# BusConOld.net
KiCad netlist of a schematic drawn in EAGLE
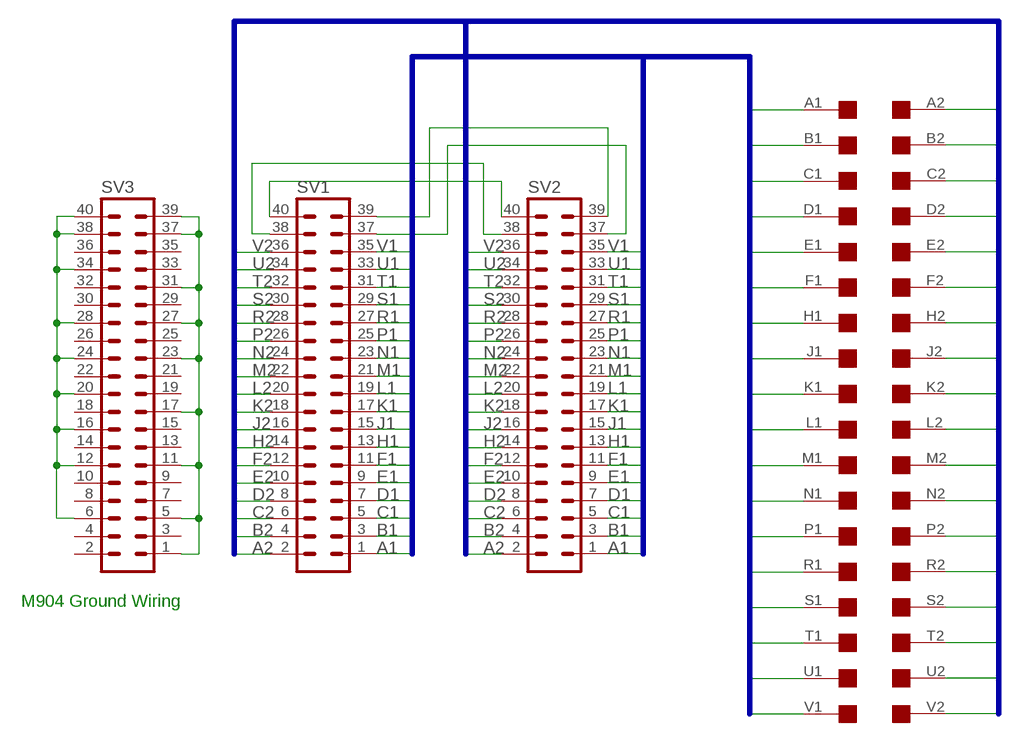
[diagram p0: schematic, sheet 1]

(export (version "E")
  (design (tool "Eeschema 10.0.6"))
  (components
    (comp (ref "SV1")
      (value "MA20-2W")
      (footprint "eagle-import:MA20-2W")
      (libsource (lib "eagle-import") (part "MA20-2W"))
    )
    (comp (ref "SV2")
      (value "MA20-2W")
      (footprint "eagle-import:MA20-2W")
      (libsource (lib "eagle-import") (part "MA20-2W"))
    )
    (comp (ref "SV3")
      (value "MA20-2W")
      (footprint "eagle-import:MA20-2W")
      (libsource (lib "eagle-import") (part "MA20-2W"))
    )
    (comp (ref "U$1")
      (value "DEC-FLIPCHIP")
      (footprint "eagle-import:DEC-FLIPCHIP")
      (libsource (lib "eagle-import") (part "DEC-FLIPCHIP"))
    )
  )
  (nets
    (net (code "1") (name "/A1") (class "Default")
      (node (ref "SV1") (pin "1") (pinfunction "1_1") (pintype "passive"))
      (node (ref "SV2") (pin "1") (pinfunction "1_1") (pintype "passive"))
      (node (ref "U$1") (pin "A1") (pinfunction "A1_A1") (pintype "passive"))
    )
    (net (code "2") (name "/A2") (class "Default")
      (node (ref "SV1") (pin "2") (pinfunction "2_2") (pintype "passive"))
      (node (ref "SV2") (pin "2") (pinfunction "2_2") (pintype "passive"))
      (node (ref "U$1") (pin "A2") (pinfunction "A2_A2") (pintype "passive"))
    )
    (net (code "3") (name "/B1") (class "Default")
      (node (ref "SV1") (pin "3") (pinfunction "3_3") (pintype "passive"))
      (node (ref "SV2") (pin "3") (pinfunction "3_3") (pintype "passive"))
      (node (ref "U$1") (pin "B1") (pinfunction "B1_B1") (pintype "passive"))
    )
    (net (code "4") (name "/B2") (class "Default")
      (node (ref "SV1") (pin "4") (pinfunction "4_4") (pintype "passive"))
      (node (ref "SV2") (pin "4") (pinfunction "4_4") (pintype "passive"))
      (node (ref "U$1") (pin "B2") (pinfunction "B2_B2") (pintype "passive"))
    )
    (net (code "5") (name "/C1") (class "Default")
      (node (ref "SV1") (pin "5") (pinfunction "5_5") (pintype "passive"))
      (node (ref "SV2") (pin "5") (pinfunction "5_5") (pintype "passive"))
      (node (ref "U$1") (pin "C1") (pinfunction "C1_C1") (pintype "passive"))
    )
    (net (code "6") (name "/C2") (class "Default")
      (node (ref "SV1") (pin "6") (pinfunction "6_6") (pintype "passive"))
      (node (ref "SV2") (pin "6") (pinfunction "6_6") (pintype "passive"))
      (node (ref "U$1") (pin "C2") (pinfunction "C2_C2") (pintype "passive"))
    )
    (net (code "7") (name "/D1") (class "Default")
      (node (ref "SV1") (pin "7") (pinfunction "7_7") (pintype "passive"))
      (node (ref "SV2") (pin "7") (pinfunction "7_7") (pintype "passive"))
      (node (ref "U$1") (pin "D1") (pinfunction "D1_D1") (pintype "passive"))
    )
    (net (code "8") (name "/D2") (class "Default")
      (node (ref "SV1") (pin "8") (pinfunction "8_8") (pintype "passive"))
      (node (ref "SV2") (pin "8") (pinfunction "8_8") (pintype "passive"))
      (node (ref "U$1") (pin "D2") (pinfunction "D2_D2") (pintype "passive"))
    )
    (net (code "9") (name "/E1") (class "Default")
      (node (ref "SV1") (pin "9") (pinfunction "9_9") (pintype "passive"))
      (node (ref "SV2") (pin "9") (pinfunction "9_9") (pintype "passive"))
      (node (ref "U$1") (pin "E1") (pinfunction "E1_E1") (pintype "passive"))
    )
    (net (code "10") (name "/E2") (class "Default")
      (node (ref "SV1") (pin "10") (pinfunction "10_10") (pintype "passive"))
      (node (ref "SV2") (pin "10") (pinfunction "10_10") (pintype "passive"))
      (node (ref "U$1") (pin "E2") (pinfunction "E2_E2") (pintype "passive"))
    )
    (net (code "11") (name "/F1") (class "Default")
      (node (ref "SV1") (pin "11") (pinfunction "11_11") (pintype "passive"))
      (node (ref "SV2") (pin "11") (pinfunction "11_11") (pintype "passive"))
      (node (ref "U$1") (pin "F1") (pinfunction "F1_F1") (pintype "passive"))
    )
    (net (code "12") (name "/F2") (class "Default")
      (node (ref "SV1") (pin "12") (pinfunction "12_12") (pintype "passive"))
      (node (ref "SV2") (pin "12") (pinfunction "12_12") (pintype "passive"))
      (node (ref "U$1") (pin "F2") (pinfunction "F2_F2") (pintype "passive"))
    )
    (net (code "13") (name "/H1") (class "Default")
      (node (ref "SV1") (pin "13") (pinfunction "13_13") (pintype "passive"))
      (node (ref "SV2") (pin "13") (pinfunction "13_13") (pintype "passive"))
      (node (ref "U$1") (pin "H1") (pinfunction "H1_H1") (pintype "passive"))
    )
    (net (code "14") (name "/H2") (class "Default")
      (node (ref "SV1") (pin "14") (pinfunction "14_14") (pintype "passive"))
      (node (ref "SV2") (pin "14") (pinfunction "14_14") (pintype "passive"))
      (node (ref "U$1") (pin "H2") (pinfunction "H2_H2") (pintype "passive"))
    )
    (net (code "15") (name "/J1") (class "Default")
      (node (ref "SV1") (pin "15") (pinfunction "15_15") (pintype "passive"))
      (node (ref "SV2") (pin "15") (pinfunction "15_15") (pintype "passive"))
      (node (ref "U$1") (pin "J1") (pinfunction "J1_J1") (pintype "passive"))
    )
    (net (code "16") (name "/J2") (class "Default")
      (node (ref "SV1") (pin "16") (pinfunction "16_16") (pintype "passive"))
      (node (ref "SV2") (pin "16") (pinfunction "16_16") (pintype "passive"))
      (node (ref "U$1") (pin "J2") (pinfunction "J2_J2") (pintype "passive"))
    )
    (net (code "17") (name "/K1") (class "Default")
      (node (ref "SV1") (pin "17") (pinfunction "17_17") (pintype "passive"))
      (node (ref "SV2") (pin "17") (pinfunction "17_17") (pintype "passive"))
      (node (ref "U$1") (pin "K1") (pinfunction "K1_K1") (pintype "passive"))
    )
    (net (code "18") (name "/K2") (class "Default")
      (node (ref "SV1") (pin "18") (pinfunction "18_18") (pintype "passive"))
      (node (ref "SV2") (pin "18") (pinfunction "18_18") (pintype "passive"))
      (node (ref "U$1") (pin "K2") (pinfunction "K2_K2") (pintype "passive"))
    )
    (net (code "19") (name "/L1") (class "Default")
      (node (ref "SV1") (pin "19") (pinfunction "19_19") (pintype "passive"))
      (node (ref "SV2") (pin "19") (pinfunction "19_19") (pintype "passive"))
      (node (ref "U$1") (pin "L1") (pinfunction "L1_L1") (pintype "passive"))
    )
    (net (code "20") (name "/L2") (class "Default")
      (node (ref "SV1") (pin "20") (pinfunction "20_20") (pintype "passive"))
      (node (ref "SV2") (pin "20") (pinfunction "20_20") (pintype "passive"))
      (node (ref "U$1") (pin "L2") (pinfunction "L2_L2") (pintype "passive"))
    )
    (net (code "21") (name "/M1") (class "Default")
      (node (ref "SV1") (pin "21") (pinfunction "21_21") (pintype "passive"))
      (node (ref "SV2") (pin "21") (pinfunction "21_21") (pintype "passive"))
      (node (ref "U$1") (pin "M1") (pinfunction "M1_M1") (pintype "passive"))
    )
    (net (code "22") (name "/M2") (class "Default")
      (node (ref "SV1") (pin "22") (pinfunction "22_22") (pintype "passive"))
      (node (ref "SV2") (pin "22") (pinfunction "22_22") (pintype "passive"))
      (node (ref "U$1") (pin "M2") (pinfunction "M2_M2") (pintype "passive"))
    )
    (net (code "23") (name "/N1") (class "Default")
      (node (ref "SV1") (pin "23") (pinfunction "23_23") (pintype "passive"))
      (node (ref "SV2") (pin "23") (pinfunction "23_23") (pintype "passive"))
      (node (ref "U$1") (pin "N1") (pinfunction "N1_N1") (pintype "passive"))
    )
    (net (code "24") (name "/N2") (class "Default")
      (node (ref "SV1") (pin "24") (pinfunction "24_24") (pintype "passive"))
      (node (ref "SV2") (pin "24") (pinfunction "24_24") (pintype "passive"))
      (node (ref "U$1") (pin "N2") (pinfunction "N2_N2") (pintype "passive"))
    )
    (net (code "25") (name "/P1") (class "Default")
      (node (ref "SV1") (pin "25") (pinfunction "25_25") (pintype "passive"))
      (node (ref "SV2") (pin "25") (pinfunction "25_25") (pintype "passive"))
      (node (ref "U$1") (pin "P1") (pinfunction "P1_P1") (pintype "passive"))
    )
    (net (code "26") (name "/P2") (class "Default")
      (node (ref "SV1") (pin "26") (pinfunction "26_26") (pintype "passive"))
      (node (ref "SV2") (pin "26") (pinfunction "26_26") (pintype "passive"))
      (node (ref "U$1") (pin "P2") (pinfunction "P2_P2") (pintype "passive"))
    )
    (net (code "27") (name "/R1") (class "Default")
      (node (ref "SV1") (pin "27") (pinfunction "27_27") (pintype "passive"))
      (node (ref "SV2") (pin "27") (pinfunction "27_27") (pintype "passive"))
      (node (ref "U$1") (pin "R1") (pinfunction "R1_R1") (pintype "passive"))
    )
    (net (code "28") (name "/R2") (class "Default")
      (node (ref "SV1") (pin "28") (pinfunction "28_28") (pintype "passive"))
      (node (ref "SV2") (pin "28") (pinfunction "28_28") (pintype "passive"))
      (node (ref "U$1") (pin "R2") (pinfunction "R2_R2") (pintype "passive"))
    )
    (net (code "29") (name "/S1") (class "Default")
      (node (ref "SV1") (pin "29") (pinfunction "29_29") (pintype "passive"))
      (node (ref "SV2") (pin "29") (pinfunction "29_29") (pintype "passive"))
      (node (ref "U$1") (pin "S1") (pinfunction "S1_S1") (pintype "passive"))
    )
    (net (code "30") (name "/S2") (class "Default")
      (node (ref "SV1") (pin "30") (pinfunction "30_30") (pintype "passive"))
      (node (ref "SV2") (pin "30") (pinfunction "30_30") (pintype "passive"))
      (node (ref "U$1") (pin "S2") (pinfunction "S2_S2") (pintype "passive"))
    )
    (net (code "31") (name "/T1") (class "Default")
      (node (ref "SV1") (pin "31") (pinfunction "31_31") (pintype "passive"))
      (node (ref "SV2") (pin "31") (pinfunction "31_31") (pintype "passive"))
      (node (ref "U$1") (pin "T1") (pinfunction "T1_T1") (pintype "passive"))
    )
    (net (code "32") (name "/T2") (class "Default")
      (node (ref "SV1") (pin "32") (pinfunction "32_32") (pintype "passive"))
      (node (ref "SV2") (pin "32") (pinfunction "32_32") (pintype "passive"))
      (node (ref "U$1") (pin "T2") (pinfunction "T2_T2") (pintype "passive"))
    )
    (net (code "33") (name "/U1") (class "Default")
      (node (ref "SV1") (pin "33") (pinfunction "33_33") (pintype "passive"))
      (node (ref "SV2") (pin "33") (pinfunction "33_33") (pintype "passive"))
      (node (ref "U$1") (pin "U1") (pinfunction "U1_U1") (pintype "passive"))
    )
    (net (code "34") (name "/U2") (class "Default")
      (node (ref "SV1") (pin "34") (pinfunction "34_34") (pintype "passive"))
      (node (ref "SV2") (pin "34") (pinfunction "34_34") (pintype "passive"))
      (node (ref "U$1") (pin "U2") (pinfunction "U2_U2") (pintype "passive"))
    )
    (net (code "35") (name "/V1") (class "Default")
      (node (ref "SV1") (pin "35") (pinfunction "35_35") (pintype "passive"))
      (node (ref "SV2") (pin "35") (pinfunction "35_35") (pintype "passive"))
      (node (ref "U$1") (pin "V1") (pinfunction "V1_V1") (pintype "passive"))
    )
    (net (code "36") (name "/V2") (class "Default")
      (node (ref "SV1") (pin "36") (pinfunction "36_36") (pintype "passive"))
      (node (ref "SV2") (pin "36") (pinfunction "36_36") (pintype "passive"))
      (node (ref "U$1") (pin "V2") (pinfunction "V2_V2") (pintype "passive"))
    )
    (net (code "37") (name "Net-(SV1-Pad37)") (class "Default")
      (node (ref "SV1") (pin "37") (pinfunction "37_37") (pintype "passive"))
      (node (ref "SV2") (pin "37") (pinfunction "37_37") (pintype "passive"))
    )
    (net (code "38") (name "Net-(SV1-Pad38)") (class "Default")
      (node (ref "SV1") (pin "38") (pinfunction "38_38") (pintype "passive"))
      (node (ref "SV2") (pin "38") (pinfunction "38_38") (pintype "passive"))
    )
    (net (code "39") (name "Net-(SV1-Pad39)") (class "Default")
      (node (ref "SV1") (pin "39") (pinfunction "39_39") (pintype "passive"))
      (node (ref "SV2") (pin "39") (pinfunction "39_39") (pintype "passive"))
    )
    (net (code "40") (name "Net-(SV1-Pad40)") (class "Default")
      (node (ref "SV1") (pin "40") (pinfunction "40_40") (pintype "passive"))
      (node (ref "SV2") (pin "40") (pinfunction "40_40") (pintype "passive"))
    )
    (net (code "41") (name "Net-(SV3-Pad1)") (class "Default")
      (node (ref "SV3") (pin "1") (pinfunction "1_1") (pintype "passive"))
      (node (ref "SV3") (pin "11") (pinfunction "11_11") (pintype "passive"))
      (node (ref "SV3") (pin "17") (pinfunction "17_17") (pintype "passive"))
      (node (ref "SV3") (pin "23") (pinfunction "23_23") (pintype "passive"))
      (node (ref "SV3") (pin "27") (pinfunction "27_27") (pintype "passive"))
      (node (ref "SV3") (pin "31") (pinfunction "31_31") (pintype "passive"))
      (node (ref "SV3") (pin "37") (pinfunction "37_37") (pintype "passive"))
      (node (ref "SV3") (pin "39") (pinfunction "39_39") (pintype "passive"))
      (node (ref "SV3") (pin "5") (pinfunction "5_5") (pintype "passive"))
    )
    (net (code "42") (name "Net-(SV3-Pad12)") (class "Default")
      (node (ref "SV3") (pin "12") (pinfunction "12_12") (pintype "passive"))
      (node (ref "SV3") (pin "16") (pinfunction "16_16") (pintype "passive"))
      (node (ref "SV3") (pin "20") (pinfunction "20_20") (pintype "passive"))
      (node (ref "SV3") (pin "24") (pinfunction "24_24") (pintype "passive"))
      (node (ref "SV3") (pin "28") (pinfunction "28_28") (pintype "passive"))
      (node (ref "SV3") (pin "34") (pinfunction "34_34") (pintype "passive"))
      (node (ref "SV3") (pin "38") (pinfunction "38_38") (pintype "passive"))
      (node (ref "SV3") (pin "40") (pinfunction "40_40") (pintype "passive"))
      (node (ref "SV3") (pin "6") (pinfunction "6_6") (pintype "passive"))
    )
    (net (code "43") (name "unconnected-(SV3-Pad2)") (class "Default")
      (node (ref "SV3") (pin "2") (pinfunction "2_2") (pintype "passive"))
    )
    (net (code "44") (name "unconnected-(SV3-Pad3)") (class "Default")
      (node (ref "SV3") (pin "3") (pinfunction "3_3") (pintype "passive"))
    )
    (net (code "45") (name "unconnected-(SV3-Pad4)") (class "Default")
      (node (ref "SV3") (pin "4") (pinfunction "4_4") (pintype "passive"))
    )
    (net (code "46") (name "unconnected-(SV3-Pad7)") (class "Default")
      (node (ref "SV3") (pin "7") (pinfunction "7_7") (pintype "passive"))
    )
    (net (code "47") (name "unconnected-(SV3-Pad8)") (class "Default")
      (node (ref "SV3") (pin "8") (pinfunction "8_8") (pintype "passive"))
    )
    (net (code "48") (name "unconnected-(SV3-Pad9)") (class "Default")
      (node (ref "SV3") (pin "9") (pinfunction "9_9") (pintype "passive"))
    )
    (net (code "49") (name "unconnected-(SV3-Pad10)") (class "Default")
      (node (ref "SV3") (pin "10") (pinfunction "10_10") (pintype "passive"))
    )
    (net (code "50") (name "unconnected-(SV3-Pad13)") (class "Default")
      (node (ref "SV3") (pin "13") (pinfunction "13_13") (pintype "passive"))
    )
    (net (code "51") (name "unconnected-(SV3-Pad14)") (class "Default")
      (node (ref "SV3") (pin "14") (pinfunction "14_14") (pintype "passive"))
    )
    (net (code "52") (name "unconnected-(SV3-Pad15)") (class "Default")
      (node (ref "SV3") (pin "15") (pinfunction "15_15") (pintype "passive"))
    )
    (net (code "53") (name "unconnected-(SV3-Pad18)") (class "Default")
      (node (ref "SV3") (pin "18") (pinfunction "18_18") (pintype "passive"))
    )
    (net (code "54") (name "unconnected-(SV3-Pad19)") (class "Default")
      (node (ref "SV3") (pin "19") (pinfunction "19_19") (pintype "passive"))
    )
    (net (code "55") (name "unconnected-(SV3-Pad21)") (class "Default")
      (node (ref "SV3") (pin "21") (pinfunction "21_21") (pintype "passive"))
    )
    (net (code "56") (name "unconnected-(SV3-Pad22)") (class "Default")
      (node (ref "SV3") (pin "22") (pinfunction "22_22") (pintype "passive"))
    )
    (net (code "57") (name "unconnected-(SV3-Pad25)") (class "Default")
      (node (ref "SV3") (pin "25") (pinfunction "25_25") (pintype "passive"))
    )
    (net (code "58") (name "unconnected-(SV3-Pad26)") (class "Default")
      (node (ref "SV3") (pin "26") (pinfunction "26_26") (pintype "passive"))
    )
    (net (code "59") (name "unconnected-(SV3-Pad29)") (class "Default")
      (node (ref "SV3") (pin "29") (pinfunction "29_29") (pintype "passive"))
    )
    (net (code "60") (name "unconnected-(SV3-Pad30)") (class "Default")
      (node (ref "SV3") (pin "30") (pinfunction "30_30") (pintype "passive"))
    )
    (net (code "61") (name "unconnected-(SV3-Pad32)") (class "Default")
      (node (ref "SV3") (pin "32") (pinfunction "32_32") (pintype "passive"))
    )
    (net (code "62") (name "unconnected-(SV3-Pad33)") (class "Default")
      (node (ref "SV3") (pin "33") (pinfunction "33_33") (pintype "passive"))
    )
    (net (code "63") (name "unconnected-(SV3-Pad35)") (class "Default")
      (node (ref "SV3") (pin "35") (pinfunction "35_35") (pintype "passive"))
    )
    (net (code "64") (name "unconnected-(SV3-Pad36)") (class "Default")
      (node (ref "SV3") (pin "36") (pinfunction "36_36") (pintype "passive"))
    )
  )
)
